# Ethernet_Interface.net
KiCad netlist of a schematic drawn in Altium Designer
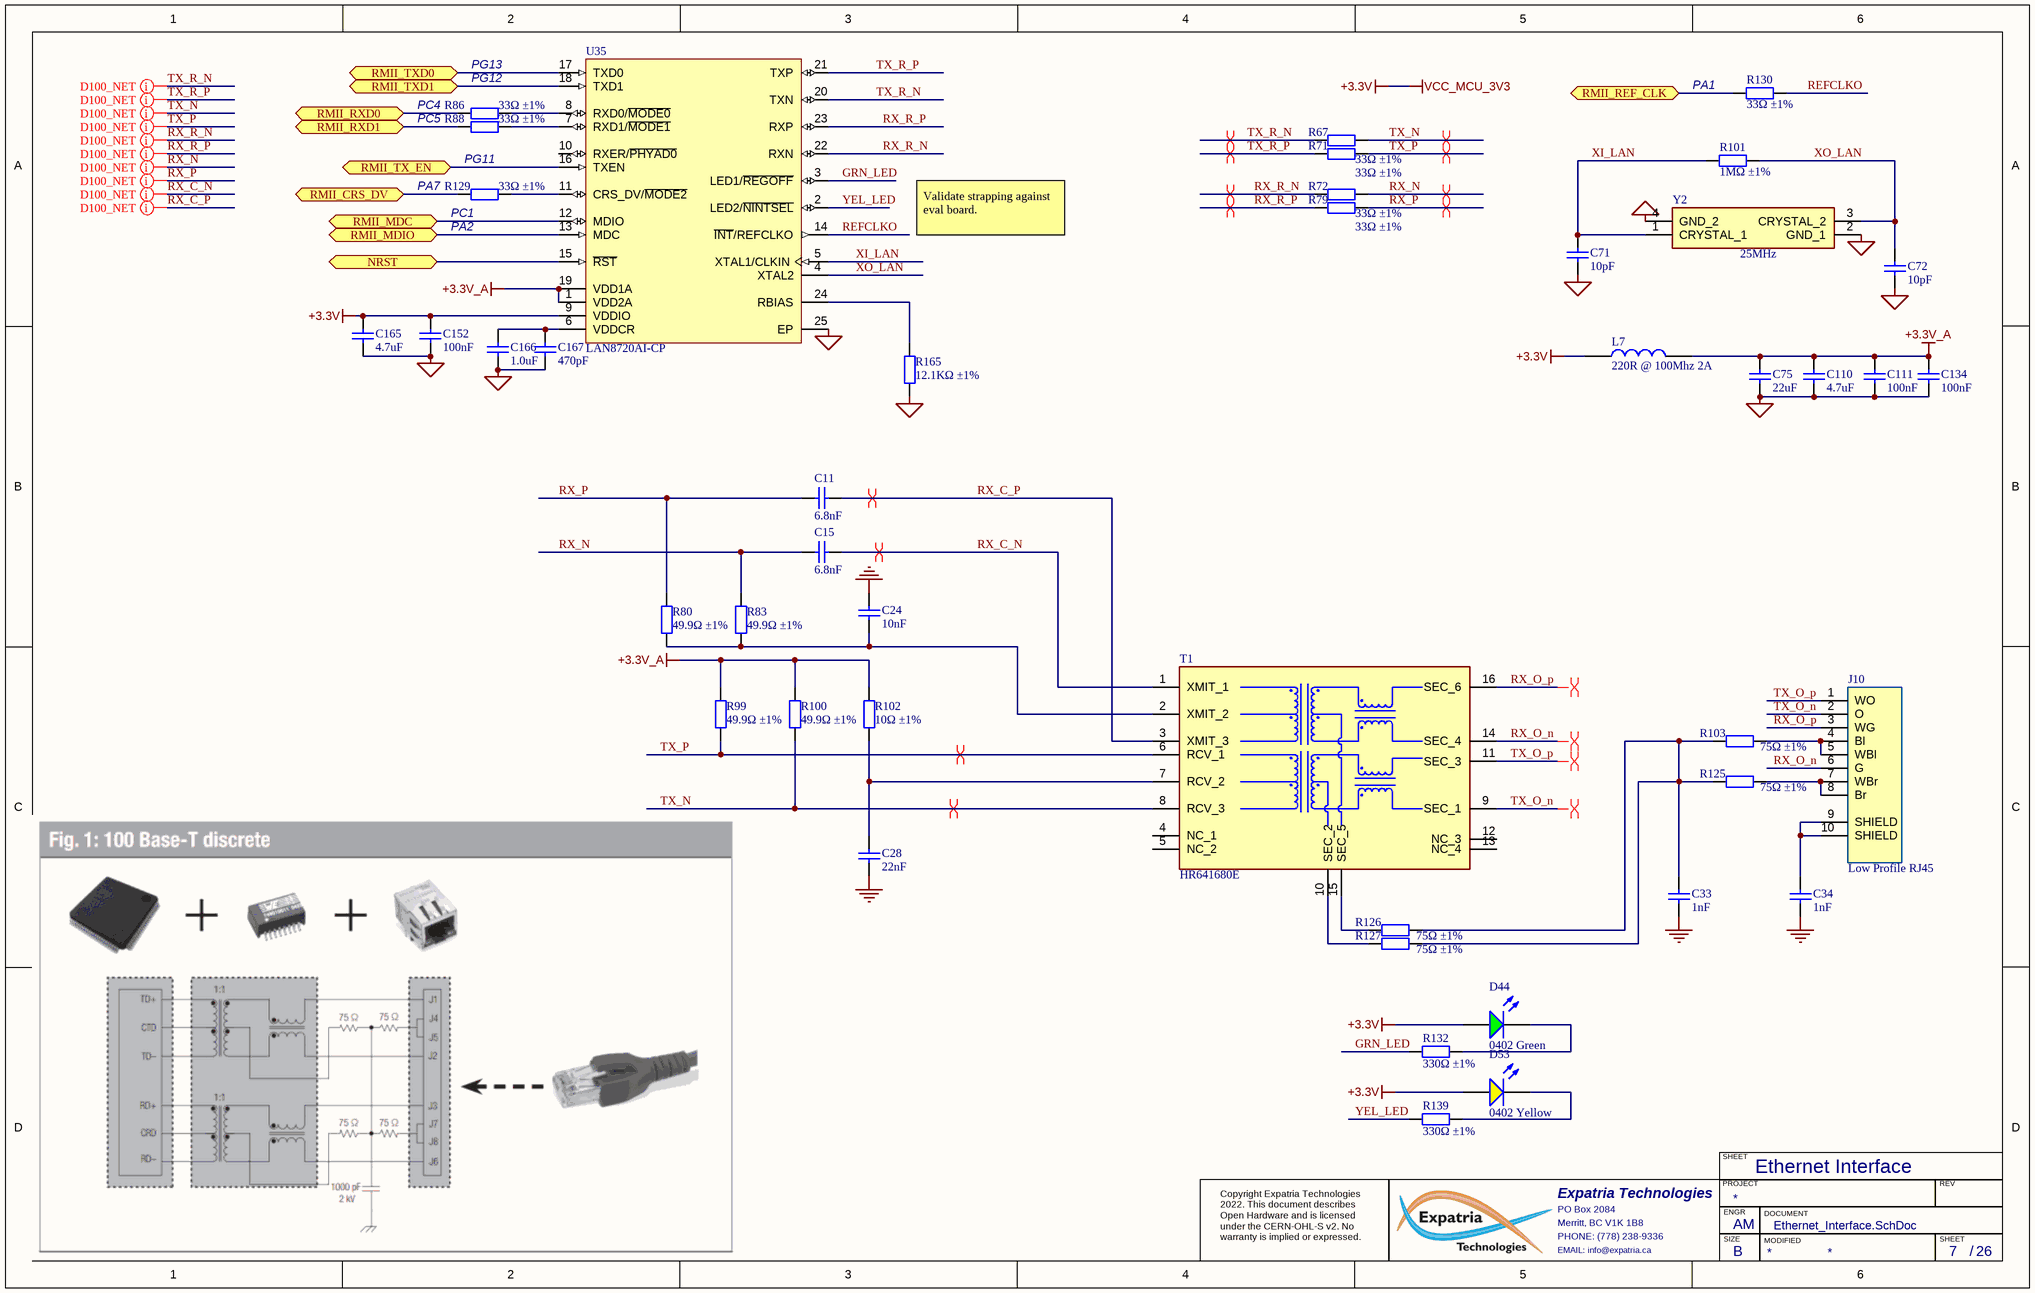
[diagram p0: Ethernet_Interface.SchDoc]

(export (version "E")
  (design (tool "Eeschema 10.0.6"))
  (components
    (comp (ref "C11")
      (value "6.8nF")
      (footprint "0402_C")
      (description "Chip capacitors")
      (fields
        (field (name "MANUFACTURER") "Guangdong Fenghua Advanced Tech")
        (field (name "PARTNUMBER") "0402B682K500NT")
      )
      (libsource (lib "Cap") (part "0402 6.8nF (682) 10% 50V"))
    )
    (comp (ref "C15")
      (value "6.8nF")
      (footprint "0402_C")
      (description "Chip capacitors")
      (fields
        (field (name "MANUFACTURER") "Guangdong Fenghua Advanced Tech")
        (field (name "PARTNUMBER") "0402B682K500NT")
      )
      (libsource (lib "Cap") (part "0402 6.8nF (682) 10% 50V"))
    )
    (comp (ref "C24")
      (value "10nF")
      (footprint "0402_C")
      (description "Chip capacitors")
      (fields
        (field (name "MANUFACTURER") "Samsung Electro-Mechanics")
        (field (name "PARTNUMBER") "CL05B103KB5NNNC")
      )
      (libsource (lib "Cap") (part "0402 10nF (103) 10% 50V"))
    )
    (comp (ref "C28")
      (value "22nF")
      (footprint "0402_C")
      (description "Chip capacitors")
      (fields
        (field (name "MANUFACTURER") "Guangdong Fenghua Advanced Tech")
        (field (name "PARTNUMBER") "0402B223K500NT")
      )
      (libsource (lib "Cap") (part "0402 22nF (223) 10% 50V"))
    )
    (comp (ref "C33")
      (value "1nF")
      (footprint "1206_C")
      (description "Chip capacitors")
      (fields
        (field (name "MANUFACTURER") "Samsung Electro-Mechanics")
        (field (name "PARTNUMBER") "CL31B102KGFNNNE")
      )
      (libsource (lib "Cap") (part "1206 1nF (102) 10% 500V"))
    )
    (comp (ref "C34")
      (value "1nF")
      (footprint "1206_C")
      (description "Chip capacitors")
      (fields
        (field (name "MANUFACTURER") "Samsung Electro-Mechanics")
        (field (name "PARTNUMBER") "CL31B102KGFNNNE")
      )
      (libsource (lib "Cap") (part "1206 1nF (102) 10% 500V"))
    )
    (comp (ref "C71")
      (value "10pF")
      (footprint "0402_C")
      (description "Chip capacitors")
      (fields
        (field (name "MANUFACTURER") "Samsung Electro-Mechanics")
        (field (name "MANUFACTURER PART NUMBER") "CL05C100JB5NNNC")
      )
      (libsource (lib "Cap") (part "0402 10pF (100) 5% 50V"))
    )
    (comp (ref "C72")
      (value "10pF")
      (footprint "0402_C")
      (description "Chip capacitors")
      (fields
        (field (name "MANUFACTURER") "Samsung Electro-Mechanics")
        (field (name "MANUFACTURER PART NUMBER") "CL05C100JB5NNNC")
      )
      (libsource (lib "Cap") (part "0402 10pF (100) 5% 50V"))
    )
    (comp (ref "C75")
      (value "22uF")
      (footprint "0805_C")
      (description "25V 22uF X5R ±20% 0805 Multilayer Ceramic Capacitors MLCC - SMD/SMT ROHS")
      (fields (field (name "MANUFACTURER") "Samsung Electro-Mechanics") (field (name "TOLERANCE") "20%"))
      (libsource (lib "Sienci_Labs") (part "0805 22uF (226) 20% 25V"))
    )
    (comp (ref "C110")
      (value "4.7uF")
      (footprint "0603_C")
      (description "16V 4.7uF X5R ±10% 0603 Multilayer Ceramic Capacitors MLCC - SMD/SMT ROHS")
      (fields (field (name "MANUFACTURER") "Samsung Electro-Mechanics") (field (name "TOLERANCE") "10%"))
      (libsource (lib "Sienci_Labs") (part "0603 4.7uF (475) 10% 16V"))
    )
    (comp (ref "C111")
      (value "100nF")
      (footprint "0402_C")
      (description "16V 100nF X7R ±10% 0402 Multilayer Ceramic Capacitors MLCC - SMD/SMT ROHS")
      (fields (field (name "MANUFACTURER") "Samsung Electro-Mechanics") (field (name "TOLERANCE") "10%"))
      (libsource (lib "Sienci_Labs") (part "0402 100nF (104) 10% 16V"))
    )
    (comp (ref "C134")
      (value "100nF")
      (footprint "0402_C")
      (description "16V 100nF X7R ±10% 0402 Multilayer Ceramic Capacitors MLCC - SMD/SMT ROHS")
      (fields (field (name "MANUFACTURER") "Samsung Electro-Mechanics") (field (name "TOLERANCE") "10%"))
      (libsource (lib "Sienci_Labs") (part "0402 100nF (104) 10% 16V"))
    )
    (comp (ref "C152")
      (value "100nF")
      (footprint "0402_C")
      (description "16V 100nF X7R ±10% 0402 Multilayer Ceramic Capacitors MLCC - SMD/SMT ROHS")
      (fields (field (name "MANUFACTURER") "Samsung Electro-Mechanics") (field (name "TOLERANCE") "10%"))
      (libsource (lib "Sienci_Labs") (part "0402 100nF (104) 10% 16V"))
    )
    (comp (ref "C165")
      (value "4.7uF")
      (footprint "0603_C")
      (description "16V 4.7uF X5R ±10% 0603 Multilayer Ceramic Capacitors MLCC - SMD/SMT ROHS")
      (fields (field (name "MANUFACTURER") "Samsung Electro-Mechanics") (field (name "TOLERANCE") "10%"))
      (libsource (lib "Sienci_Labs") (part "0603 4.7uF (475) 10% 16V"))
    )
    (comp (ref "C166")
      (value "1.0uF")
      (footprint "0402_C")
      (description "Chip capacitor")
      (fields
        (field (name "MANUFACTURER") "Samsung Electro-Mechanics")
        (field (name "PARTNUMBER") "CL05A105KA5NQNC")
      )
      (libsource (lib "Cap") (part "0402 1.0uF (105) 10% 25V"))
    )
    (comp (ref "C167")
      (value "470pF")
      (footprint "0402_C")
      (description "Chip capacitors")
      (fields
        (field (name "MANUFACTURER") "Guangdong Fenghua Advanced Tech")
        (field (name "PARTNUMBER") "0402B471K500NT")
      )
      (libsource (lib "Cap") (part "0402 470pF (471) 10% 50V"))
    )
    (comp (ref "D44")
      (value "0402 Green")
      (footprint "LED 0402_1005 RED")
      (description "LED")
      (libsource (lib "LED") (part "0402 LED Green"))
    )
    (comp (ref "D53")
      (value "0402 Yellow")
      (footprint "LED 0402_1005 RED")
      (description "LED")
      (libsource (lib "LED") (part "0402 LED Yellow"))
    )
    (comp (ref "J10")
      (value "Low Profile RJ45")
      (footprint "RJ45-SMD_MJ88-B011-HLSV6-P")
      (description "Micro USB")
      (fields (field (name "MF") "Heling"))
      (libsource (lib "Universal_CNC_Breakout") (part "MJ88-B011-HLSV6-P"))
    )
    (comp (ref "L7")
      (value "220R @ 100Mhz 2A")
      (footprint "0805_R")
      (description "150mΩ ±25% 220Ω@100MHz 0805 Ferrite Beads ROHS")
      (fields
        (field (name "MANUFACTURER PART NUMBER") "CBW201209U221T")
        (field (name "MANUFACTURER") "FH (Guangdong Fenghua Advanced Tech)")
      )
      (libsource (lib "Sienci_Labs") (part "CBW201209U221T"))
    )
    (comp (ref "R67")
      (value "33Ω ±1%")
      (footprint "0402_R")
      (description "Chip resistor")
      (fields
        (field (name "MANUFACTURER") "Uniroyal Elec")
        (field (name "MANUFACTURER PART NUMBER") "0402WGF330JTCE")
      )
      (libsource (lib "") (part "0402 33R (33R0) 1%_1"))
    )
    (comp (ref "R71")
      (value "33Ω ±1%")
      (footprint "0402_R")
      (description "Chip resistor")
      (fields
        (field (name "MANUFACTURER") "Uniroyal Elec")
        (field (name "MANUFACTURER PART NUMBER") "0402WGF330JTCE")
      )
      (libsource (lib "") (part "0402 33R (33R0) 1%_1"))
    )
    (comp (ref "R72")
      (value "33Ω ±1%")
      (footprint "0402_R")
      (description "Chip resistor")
      (fields
        (field (name "MANUFACTURER") "Uniroyal Elec")
        (field (name "MANUFACTURER PART NUMBER") "0402WGF330JTCE")
      )
      (libsource (lib "") (part "0402 33R (33R0) 1%_1"))
    )
    (comp (ref "R79")
      (value "33Ω ±1%")
      (footprint "0402_R")
      (description "Chip resistor")
      (fields
        (field (name "MANUFACTURER") "Uniroyal Elec")
        (field (name "MANUFACTURER PART NUMBER") "0402WGF330JTCE")
      )
      (libsource (lib "") (part "0402 33R (33R0) 1%_1"))
    )
    (comp (ref "R80")
      (value "49.9Ω ±1%")
      (footprint "0402_R")
      (description "Chip resistor")
      (fields (field (name "MANUFACTURER") "Uniroyal Elec") (field (name "PARTNUMBER") "0402WGF499JTCE"))
      (libsource (lib "RES") (part "0402 49.9R (49R9) 1%"))
    )
    (comp (ref "R83")
      (value "49.9Ω ±1%")
      (footprint "0402_R")
      (description "Chip resistor")
      (fields (field (name "MANUFACTURER") "Uniroyal Elec") (field (name "PARTNUMBER") "0402WGF499JTCE"))
      (libsource (lib "RES") (part "0402 49.9R (49R9) 1%"))
    )
    (comp (ref "R86")
      (value "33Ω ±1%")
      (footprint "0402_R")
      (description "Chip resistor")
      (fields
        (field (name "MANUFACTURER") "Uniroyal Elec")
        (field (name "MANUFACTURER PART NUMBER") "0402WGF330JTCE")
      )
      (libsource (lib "RES") (part "0402 33R (33R0) 1%"))
    )
    (comp (ref "R88")
      (value "33Ω ±1%")
      (footprint "0402_R")
      (description "Chip resistor")
      (fields
        (field (name "MANUFACTURER") "Uniroyal Elec")
        (field (name "MANUFACTURER PART NUMBER") "0402WGF330JTCE")
      )
      (libsource (lib "RES") (part "0402 33R (33R0) 1%"))
    )
    (comp (ref "R99")
      (value "49.9Ω ±1%")
      (footprint "0402_R")
      (description "Chip resistor")
      (fields (field (name "MANUFACTURER") "Uniroyal Elec") (field (name "PARTNUMBER") "0402WGF499JTCE"))
      (libsource (lib "") (part "0402 49.9R (49R9) 1%_1"))
    )
    (comp (ref "R100")
      (value "49.9Ω ±1%")
      (footprint "0402_R")
      (description "Chip resistor")
      (fields (field (name "MANUFACTURER") "Uniroyal Elec") (field (name "PARTNUMBER") "0402WGF499JTCE"))
      (libsource (lib "") (part "0402 49.9R (49R9) 1%_1"))
    )
    (comp (ref "R101")
      (value "1MΩ ±1%")
      (footprint "0402_R")
      (description "Chip resistor")
      (fields
        (field (name "MANUFACTURER") "Uniroyal Elec")
        (field (name "MANUFACTURER PART NUMBER") "0402WGF1004TCE")
      )
      (libsource (lib "RES") (part "0402 1M (1004) 1%"))
    )
    (comp (ref "R102")
      (value "10Ω ±1%")
      (footprint "0402_R")
      (description "Chip resistor")
      (fields (field (name "MANUFACTURER") "Uniroyal Elec") (field (name "PARTNUMBER") "0402WGF100JTCE"))
      (libsource (lib "RES") (part "0402 10R (10R0) 1%"))
    )
    (comp (ref "R103")
      (value "75Ω ±1%")
      (footprint "0402_R")
      (description "Chip resistor")
      (fields (field (name "MANUFACTURER") "Uniroyal Elec") (field (name "PARTNUMBER") "0402WGF750JTCE"))
      (libsource (lib "RES") (part "0402 75R (75R0) 1%"))
    )
    (comp (ref "R125")
      (value "75Ω ±1%")
      (footprint "0402_R")
      (description "Chip resistor")
      (fields (field (name "MANUFACTURER") "Uniroyal Elec") (field (name "PARTNUMBER") "0402WGF750JTCE"))
      (libsource (lib "RES") (part "0402 75R (75R0) 1%"))
    )
    (comp (ref "R126")
      (value "75Ω ±1%")
      (footprint "0402_R")
      (description "Chip resistor")
      (fields (field (name "MANUFACTURER") "Uniroyal Elec") (field (name "PARTNUMBER") "0402WGF750JTCE"))
      (libsource (lib "RES") (part "0402 75R (75R0) 1%"))
    )
    (comp (ref "R127")
      (value "75Ω ±1%")
      (footprint "0402_R")
      (description "Chip resistor")
      (fields (field (name "MANUFACTURER") "Uniroyal Elec") (field (name "PARTNUMBER") "0402WGF750JTCE"))
      (libsource (lib "RES") (part "0402 75R (75R0) 1%"))
    )
    (comp (ref "R129")
      (value "33Ω ±1%")
      (footprint "0402_R")
      (description "Chip resistor")
      (fields
        (field (name "MANUFACTURER") "Uniroyal Elec")
        (field (name "MANUFACTURER PART NUMBER") "0402WGF330JTCE")
      )
      (libsource (lib "RES") (part "0402 33R (33R0) 1%"))
    )
    (comp (ref "R130")
      (value "33Ω ±1%")
      (footprint "0402_R")
      (description "Chip resistor")
      (fields
        (field (name "MANUFACTURER") "Uniroyal Elec")
        (field (name "MANUFACTURER PART NUMBER") "0402WGF330JTCE")
      )
      (libsource (lib "RES") (part "0402 33R (33R0) 1%"))
    )
    (comp (ref "R132")
      (value "330Ω ±1%")
      (footprint "0402_R")
      (description "Chip resistor")
      (fields (field (name "MANUFACTURER") "Uniroyal Elec") (field (name "PARTNUMBER") "0402WGF3300TCE"))
      (libsource (lib "RES") (part "0402 330R (3300) 1%"))
    )
    (comp (ref "R139")
      (value "330Ω ±1%")
      (footprint "0402_R")
      (description "Chip resistor")
      (fields (field (name "MANUFACTURER") "Uniroyal Elec") (field (name "PARTNUMBER") "0402WGF3300TCE"))
      (libsource (lib "RES") (part "0402 330R (3300) 1%"))
    )
    (comp (ref "R165")
      (value "12.1KΩ ±1%")
      (footprint "0805_R")
      (description "Chip resistor")
      (fields (field (name "MANUFACTURER") "Uniroyal Elec") (field (name "POWER") "1/8W"))
      (libsource (lib "RES") (part "0805 12.1K (1212) 1%"))
    )
    (comp (ref "T1")
      (value "HR641680E")
      (footprint "SamacSys:HR641680E")
      (description "Transformer")
      (libsource (lib "Universal_CNC_Breakout") (part "HR641680E"))
    )
    (comp (ref "U35")
      (value "LAN8720AI-CP")
      (footprint "MCHP-QFN-24_V")
      (description "RMII 10/100 Ethernet Transceiver with HP Auto-MDIX Support, -40 to 85 degC, 24-Pin QFN, RoHS, Tray")
      (fields (field (name "MANUFACTURER") "Microchip"))
      (libsource (lib "Altium Content Vault") (part "MCHP-LAN8720AX"))
    )
    (comp (ref "Y2")
      (value "25MHz")
      (footprint "YSX321SL")
      (description "25MHz SMD Crystal Resonator 20pF ±10ppm ±30ppm -40℃~+85℃ SMD3225-4P Crystals ROHS")
      (fields
        (field (name "MANUFACTURER") "Yangxing Tech")
        (field (name "MANUFACTURER PART NUMBER") "X322525MSB4SI")
      )
      (libsource (lib "Sienci_Labs") (part "X322525MSB4SI"))
    )
  )
  (nets
    (net (code "1") (name "+3.3V") (class "Default")
      (node (ref "C152") (pin "2") (pinfunction "2_2") (pintype "passive"))
      (node (ref "C165") (pin "2") (pinfunction "2_2") (pintype "passive"))
      (node (ref "D44") (pin "A") (pinfunction "A_A") (pintype "passive"))
      (node (ref "D53") (pin "A") (pinfunction "A_A") (pintype "passive"))
      (node (ref "L7") (pin "1") (pinfunction "1_1") (pintype "passive"))
      (node (ref "U35") (pin "9") (pinfunction "VDDIO_9") (pintype "power_in"))
    )
    (net (code "2") (name "+3.3V_A") (class "Default")
      (node (ref "C110") (pin "2") (pinfunction "2_2") (pintype "passive"))
      (node (ref "C111") (pin "2") (pinfunction "2_2") (pintype "passive"))
      (node (ref "C134") (pin "2") (pinfunction "2_2") (pintype "passive"))
      (node (ref "C75") (pin "2") (pinfunction "2_2") (pintype "passive"))
      (node (ref "L7") (pin "2") (pinfunction "2_2") (pintype "passive"))
      (node (ref "R100") (pin "1") (pinfunction "1_1") (pintype "passive"))
      (node (ref "R102") (pin "1") (pinfunction "1_1") (pintype "passive"))
      (node (ref "R99") (pin "1") (pinfunction "1_1") (pintype "passive"))
      (node (ref "U35") (pin "1") (pinfunction "VDD2A_1") (pintype "power_in"))
      (node (ref "U35") (pin "19") (pinfunction "VDD1A_19") (pintype "power_in"))
    )
    (net (code "3") (name "/GRN_LED") (class "Default")
      (node (ref "R132") (pin "1") (pinfunction "1_1") (pintype "passive"))
      (node (ref "U35") (pin "3") (pinfunction "LED1/~{REGOFF}_3") (pintype "bidirectional"))
    )
    (net (code "4") (name "/NRST") (class "Default")
      (node (ref "U35") (pin "15") (pinfunction "~{RST}_15") (pintype "input"))
    )
    (net (code "5") (name "/REFCLKO") (class "Default")
      (node (ref "R130") (pin "2") (pinfunction "2_2") (pintype "passive"))
      (node (ref "U35") (pin "14") (pinfunction "~{INT}/REFCLKO_14") (pintype "output"))
    )
    (net (code "6") (name "/RMII_CRS_DV") (class "Default")
      (node (ref "R129") (pin "1") (pinfunction "1_1") (pintype "passive"))
    )
    (net (code "7") (name "/RMII_MDC") (class "Default")
      (node (ref "U35") (pin "12") (pinfunction "MDIO_12") (pintype "bidirectional"))
    )
    (net (code "8") (name "/RMII_MDIO") (class "Default")
      (node (ref "U35") (pin "13") (pinfunction "MDC_13") (pintype "input"))
    )
    (net (code "9") (name "/RMII_REF_CLK") (class "Default")
      (node (ref "R130") (pin "1") (pinfunction "1_1") (pintype "passive"))
    )
    (net (code "10") (name "/RMII_RXD0") (class "Default")
      (node (ref "R86") (pin "1") (pinfunction "1_1") (pintype "passive"))
    )
    (net (code "11") (name "/RMII_RXD1") (class "Default")
      (node (ref "R88") (pin "1") (pinfunction "1_1") (pintype "passive"))
    )
    (net (code "12") (name "/RMII_TXD0") (class "Default")
      (node (ref "U35") (pin "17") (pinfunction "TXD0_17") (pintype "input"))
    )
    (net (code "13") (name "/RMII_TXD1") (class "Default")
      (node (ref "U35") (pin "18") (pinfunction "TXD1_18") (pintype "input"))
    )
    (net (code "14") (name "/RMII_TX_EN") (class "Default")
      (node (ref "U35") (pin "16") (pinfunction "TXEN_16") (pintype "input"))
    )
    (net (code "15") (name "/RX_C_N") (class "Default")
      (node (ref "C15") (pin "1") (pinfunction "1_1") (pintype "passive"))
      (node (ref "T1") (pin "1") (pinfunction "XMIT_1_1") (pintype "passive"))
    )
    (net (code "16") (name "/RX_C_P") (class "Default")
      (node (ref "C11") (pin "1") (pinfunction "1_1") (pintype "passive"))
      (node (ref "T1") (pin "3") (pinfunction "XMIT_3_3") (pintype "passive"))
    )
    (net (code "17") (name "/RX_N") (class "Default")
      (node (ref "C15") (pin "2") (pinfunction "2_2") (pintype "passive"))
      (node (ref "R72") (pin "1") (pinfunction "1_1") (pintype "passive"))
      (node (ref "R83") (pin "2") (pinfunction "2_2") (pintype "passive"))
    )
    (net (code "18") (name "/RX_O_n") (class "Default")
      (node (ref "J10") (pin "6") (pinfunction "G_6") (pintype "passive"))
      (node (ref "T1") (pin "14") (pinfunction "SEC_4_14") (pintype "passive"))
    )
    (net (code "19") (name "/RX_O_p") (class "Default")
      (node (ref "J10") (pin "3") (pinfunction "WG_3") (pintype "passive"))
      (node (ref "T1") (pin "16") (pinfunction "SEC_6_16") (pintype "passive"))
    )
    (net (code "20") (name "/RX_P") (class "Default")
      (node (ref "C11") (pin "2") (pinfunction "2_2") (pintype "passive"))
      (node (ref "R79") (pin "1") (pinfunction "1_1") (pintype "passive"))
      (node (ref "R80") (pin "2") (pinfunction "2_2") (pintype "passive"))
    )
    (net (code "21") (name "/RX_R_N") (class "Default")
      (node (ref "R72") (pin "2") (pinfunction "2_2") (pintype "passive"))
      (node (ref "U35") (pin "22") (pinfunction "RXN_22") (pintype "bidirectional"))
    )
    (net (code "22") (name "/RX_R_P") (class "Default")
      (node (ref "R79") (pin "2") (pinfunction "2_2") (pintype "passive"))
      (node (ref "U35") (pin "23") (pinfunction "RXP_23") (pintype "bidirectional"))
    )
    (net (code "23") (name "/TX_N") (class "Default")
      (node (ref "R100") (pin "2") (pinfunction "2_2") (pintype "passive"))
      (node (ref "R67") (pin "1") (pinfunction "1_1") (pintype "passive"))
      (node (ref "T1") (pin "8") (pinfunction "RCV_3_8") (pintype "passive"))
    )
    (net (code "24") (name "/TX_O_n") (class "Default")
      (node (ref "J10") (pin "2") (pinfunction "O_2") (pintype "passive"))
      (node (ref "T1") (pin "9") (pinfunction "SEC_1_9") (pintype "passive"))
    )
    (net (code "25") (name "/TX_O_p") (class "Default")
      (node (ref "J10") (pin "1") (pinfunction "WO_1") (pintype "power_in"))
      (node (ref "T1") (pin "11") (pinfunction "SEC_3_11") (pintype "passive"))
    )
    (net (code "26") (name "/TX_P") (class "Default")
      (node (ref "R71") (pin "1") (pinfunction "1_1") (pintype "passive"))
      (node (ref "R99") (pin "2") (pinfunction "2_2") (pintype "passive"))
      (node (ref "T1") (pin "6") (pinfunction "RCV_1_6") (pintype "passive"))
    )
    (net (code "27") (name "/TX_R_N") (class "Default")
      (node (ref "R67") (pin "2") (pinfunction "2_2") (pintype "passive"))
      (node (ref "U35") (pin "20") (pinfunction "TXN_20") (pintype "bidirectional"))
    )
    (net (code "28") (name "/TX_R_P") (class "Default")
      (node (ref "R71") (pin "2") (pinfunction "2_2") (pintype "passive"))
      (node (ref "U35") (pin "21") (pinfunction "TXP_21") (pintype "bidirectional"))
    )
    (net (code "29") (name "/XI_LAN") (class "Default")
      (node (ref "C71") (pin "2") (pinfunction "2_2") (pintype "passive"))
      (node (ref "R101") (pin "1") (pinfunction "1_1") (pintype "passive"))
      (node (ref "U35") (pin "5") (pinfunction "XTAL1/CLKIN_5") (pintype "input"))
      (node (ref "Y2") (pin "1") (pinfunction "CRYSTAL_1_1") (pintype "passive"))
    )
    (net (code "30") (name "/XO_LAN") (class "Default")
      (node (ref "C72") (pin "2") (pinfunction "2_2") (pintype "passive"))
      (node (ref "R101") (pin "2") (pinfunction "2_2") (pintype "passive"))
      (node (ref "U35") (pin "4") (pinfunction "XTAL2_4") (pintype "passive"))
      (node (ref "Y2") (pin "3") (pinfunction "CRYSTAL_2_3") (pintype "passive"))
    )
    (net (code "31") (name "/YEL_LED") (class "Default")
      (node (ref "R139") (pin "1") (pinfunction "1_1") (pintype "passive"))
      (node (ref "U35") (pin "2") (pinfunction "LED2/~{NINTSEL}_2") (pintype "bidirectional"))
    )
    (net (code "32") (name "GND") (class "Default")
      (node (ref "C24") (pin "1") (pinfunction "1_1") (pintype "passive"))
      (node (ref "C28") (pin "1") (pinfunction "1_1") (pintype "passive"))
      (node (ref "C33") (pin "1") (pinfunction "1_1") (pintype "passive"))
      (node (ref "C34") (pin "1") (pinfunction "1_1") (pintype "passive"))
    )
    (net (code "33") (name "MCU_GND") (class "Default")
      (node (ref "C110") (pin "1") (pinfunction "1_1") (pintype "passive"))
      (node (ref "C111") (pin "1") (pinfunction "1_1") (pintype "passive"))
      (node (ref "C134") (pin "1") (pinfunction "1_1") (pintype "passive"))
      (node (ref "C152") (pin "1") (pinfunction "1_1") (pintype "passive"))
      (node (ref "C165") (pin "1") (pinfunction "1_1") (pintype "passive"))
      (node (ref "C166") (pin "1") (pinfunction "1_1") (pintype "passive"))
      (node (ref "C167") (pin "1") (pinfunction "1_1") (pintype "passive"))
      (node (ref "C71") (pin "1") (pinfunction "1_1") (pintype "passive"))
      (node (ref "C72") (pin "1") (pinfunction "1_1") (pintype "passive"))
      (node (ref "C75") (pin "1") (pinfunction "1_1") (pintype "passive"))
      (node (ref "R165") (pin "1") (pinfunction "1_1") (pintype "passive"))
      (node (ref "U35") (pin "25") (pinfunction "EP_25") (pintype "power_in"))
      (node (ref "Y2") (pin "2") (pinfunction "GND_1_2") (pintype "passive"))
      (node (ref "Y2") (pin "4") (pinfunction "GND_2_4") (pintype "passive"))
    )
    (net (code "34") (name "Net-(C33-Pad2)") (class "Default")
      (node (ref "C33") (pin "2") (pinfunction "2_2") (pintype "passive"))
      (node (ref "R103") (pin "2") (pinfunction "2_2") (pintype "passive"))
      (node (ref "R125") (pin "2") (pinfunction "2_2") (pintype "passive"))
      (node (ref "R126") (pin "1") (pinfunction "1_1") (pintype "passive"))
      (node (ref "R127") (pin "1") (pinfunction "1_1") (pintype "passive"))
    )
    (net (code "35") (name "Net-(C34-Pad2)") (class "Default")
      (node (ref "C34") (pin "2") (pinfunction "2_2") (pintype "passive"))
      (node (ref "J10") (pin "10") (pinfunction "SHIELD_10") (pintype "passive"))
      (node (ref "J10") (pin "9") (pinfunction "SHIELD_9") (pintype "passive"))
    )
    (net (code "36") (name "Net-(D44-PadK)") (class "Default")
      (node (ref "D44") (pin "K") (pinfunction "K_K") (pintype "passive"))
      (node (ref "R132") (pin "2") (pinfunction "2_2") (pintype "passive"))
    )
    (net (code "37") (name "Net-(D53-PadK)") (class "Default")
      (node (ref "D53") (pin "K") (pinfunction "K_K") (pintype "passive"))
      (node (ref "R139") (pin "2") (pinfunction "2_2") (pintype "passive"))
    )
    (net (code "38") (name "Net-(J10-Bl)") (class "Default")
      (node (ref "J10") (pin "4") (pinfunction "Bl_4") (pintype "passive"))
      (node (ref "J10") (pin "5") (pinfunction "WBl_5") (pintype "power_in"))
      (node (ref "R103") (pin "1") (pinfunction "1_1") (pintype "passive"))
    )
    (net (code "39") (name "Net-(J10-Br)") (class "Default")
      (node (ref "J10") (pin "7") (pinfunction "WBr_7") (pintype "passive"))
      (node (ref "J10") (pin "8") (pinfunction "Br_8") (pintype "passive"))
      (node (ref "R125") (pin "1") (pinfunction "1_1") (pintype "passive"))
    )
    (net (code "40") (name "Net-(T1-RCV_2)") (class "Default")
      (node (ref "C28") (pin "2") (pinfunction "2_2") (pintype "passive"))
      (node (ref "R102") (pin "2") (pinfunction "2_2") (pintype "passive"))
      (node (ref "T1") (pin "7") (pinfunction "RCV_2_7") (pintype "passive"))
    )
    (net (code "41") (name "Net-(T1-SEC_2)") (class "Default")
      (node (ref "R127") (pin "2") (pinfunction "2_2") (pintype "passive"))
      (node (ref "T1") (pin "10") (pinfunction "SEC_2_10") (pintype "passive"))
    )
    (net (code "42") (name "Net-(T1-SEC_5)") (class "Default")
      (node (ref "R126") (pin "2") (pinfunction "2_2") (pintype "passive"))
      (node (ref "T1") (pin "15") (pinfunction "SEC_5_15") (pintype "passive"))
    )
    (net (code "43") (name "Net-(T1-XMIT_2)") (class "Default")
      (node (ref "C24") (pin "2") (pinfunction "2_2") (pintype "passive"))
      (node (ref "R80") (pin "1") (pinfunction "1_1") (pintype "passive"))
      (node (ref "R83") (pin "1") (pinfunction "1_1") (pintype "passive"))
      (node (ref "T1") (pin "2") (pinfunction "XMIT_2_2") (pintype "passive"))
    )
    (net (code "44") (name "Net-(U35-CRS_DV{slash}~{MODE2})") (class "Default")
      (node (ref "R129") (pin "2") (pinfunction "2_2") (pintype "passive"))
      (node (ref "U35") (pin "11") (pinfunction "CRS_DV/~{MODE2}_11") (pintype "bidirectional"))
    )
    (net (code "45") (name "Net-(U35-RBIAS)") (class "Default")
      (node (ref "R165") (pin "2") (pinfunction "2_2") (pintype "passive"))
      (node (ref "U35") (pin "24") (pinfunction "RBIAS_24") (pintype "passive"))
    )
    (net (code "46") (name "Net-(U35-RXD0{slash}~{MODE0})") (class "Default")
      (node (ref "R86") (pin "2") (pinfunction "2_2") (pintype "passive"))
      (node (ref "U35") (pin "8") (pinfunction "RXD0/~{MODE0}_8") (pintype "bidirectional"))
    )
    (net (code "47") (name "Net-(U35-RXD1{slash}~{MODE1})") (class "Default")
      (node (ref "R88") (pin "2") (pinfunction "2_2") (pintype "passive"))
      (node (ref "U35") (pin "7") (pinfunction "RXD1/~{MODE1}_7") (pintype "bidirectional"))
    )
    (net (code "48") (name "Net-(U35-VDDCR)") (class "Default")
      (node (ref "C166") (pin "2") (pinfunction "2_2") (pintype "passive"))
      (node (ref "C167") (pin "2") (pinfunction "2_2") (pintype "passive"))
      (node (ref "U35") (pin "6") (pinfunction "VDDCR_6") (pintype "power_in"))
    )
    (net (code "49") (name "unconnected-(T1-NC_1-Pad4)") (class "Default")
      (node (ref "T1") (pin "4") (pinfunction "NC_1_4") (pintype "passive"))
    )
    (net (code "50") (name "unconnected-(T1-NC_2-Pad5)") (class "Default")
      (node (ref "T1") (pin "5") (pinfunction "NC_2_5") (pintype "passive"))
    )
    (net (code "51") (name "unconnected-(T1-NC_3-Pad12)") (class "Default")
      (node (ref "T1") (pin "12") (pinfunction "NC_3_12") (pintype "passive"))
    )
    (net (code "52") (name "unconnected-(T1-NC_4-Pad13)") (class "Default")
      (node (ref "T1") (pin "13") (pinfunction "NC_4_13") (pintype "passive"))
    )
    (net (code "53") (name "unconnected-(U35-RXER{slash}~{PHYAD0}-Pad10)") (class "Default")
      (node (ref "U35") (pin "10") (pinfunction "RXER/~{PHYAD0}_10") (pintype "bidirectional"))
    )
  )
)
